# slambot.net
KiCad netlist of a schematic drawn in EAGLE
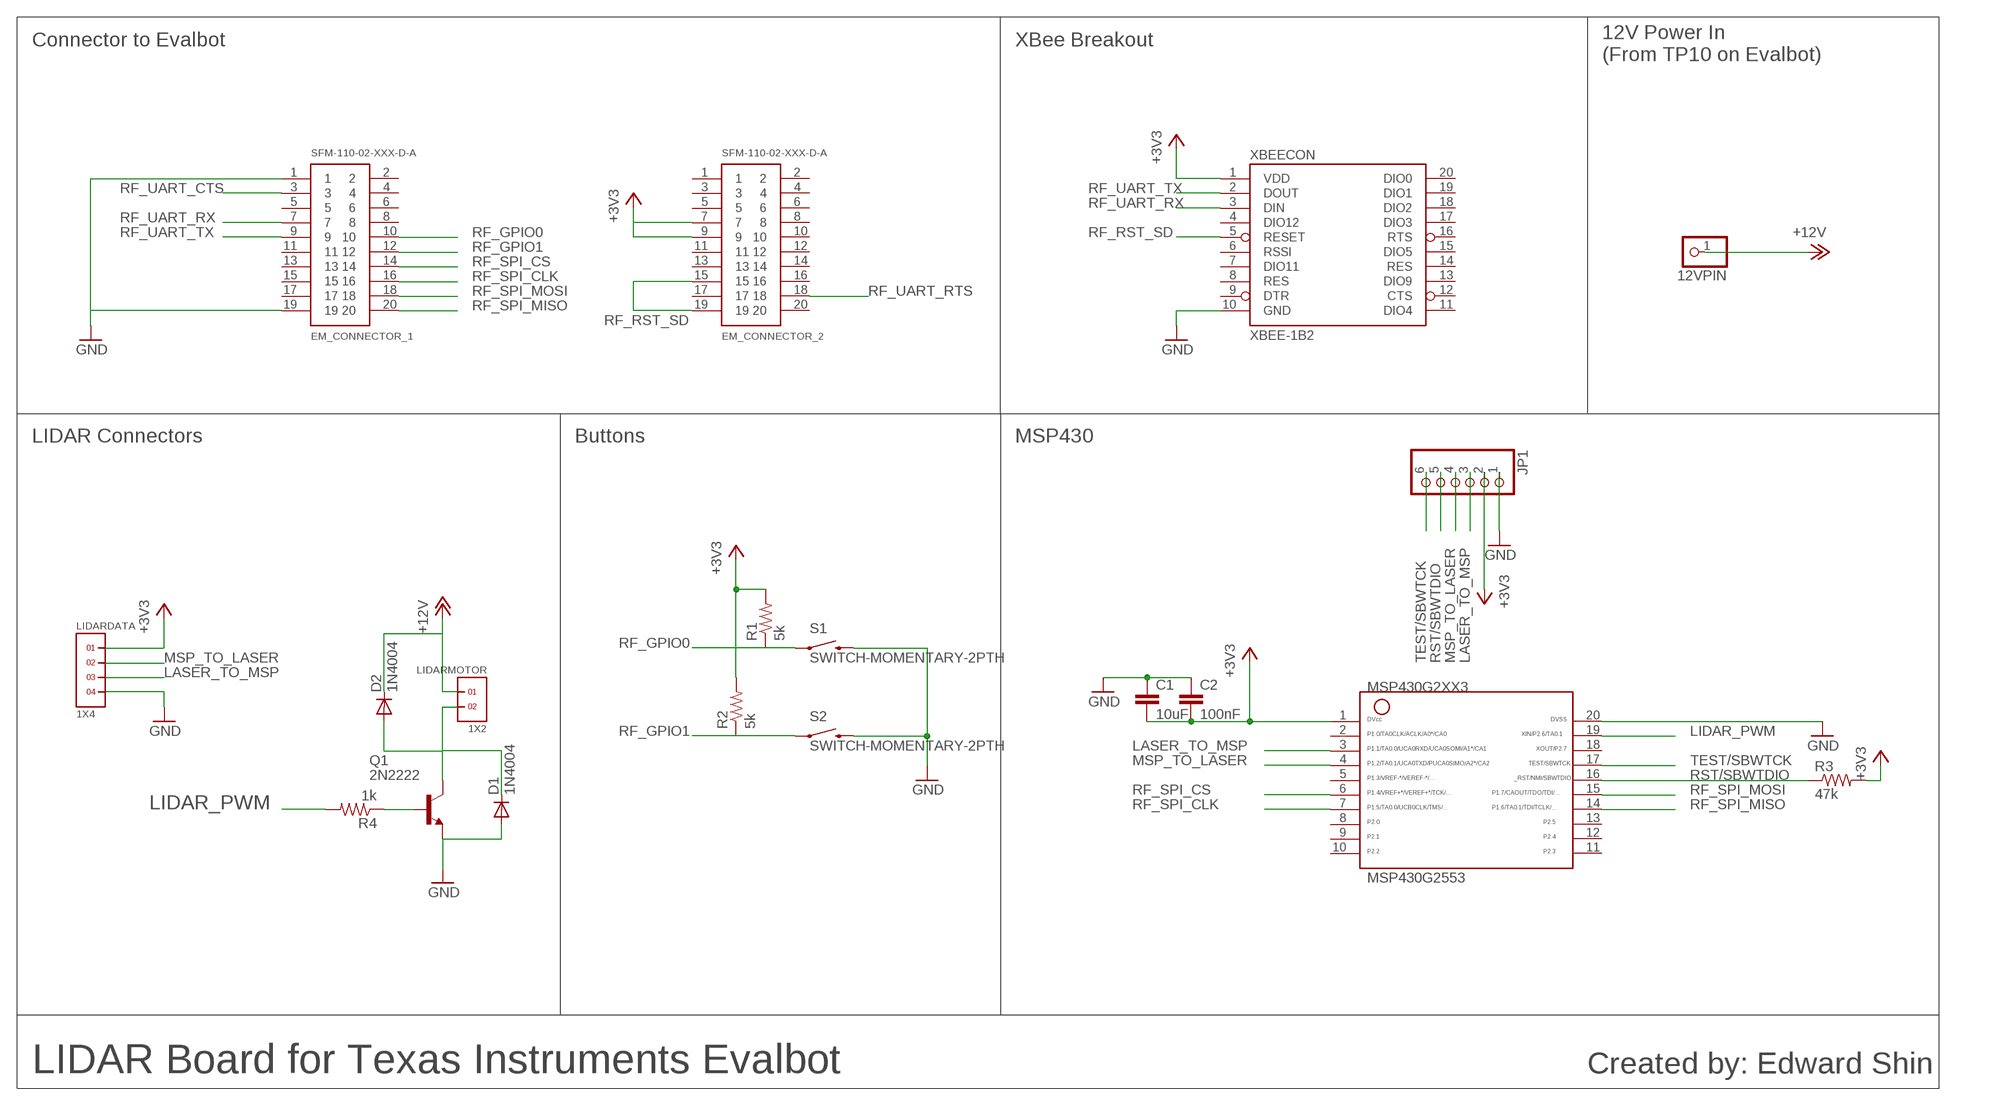
[diagram p0: schematic, sheet 1]

(export (version "E")
  (design (tool "Eeschema 10.0.6"))
  (components
    (comp (ref "12VPIN")
      (value "PINHD-1X1")
      (footprint "eagle-import:1X01")
      (libsource (lib "eagle-import") (part "PINHD-1X1"))
    )
    (comp (ref "C1")
      (value "10uF")
      (footprint "eagle-import:C2.5-2")
      (libsource (lib "eagle-import") (part "C2.5/2"))
    )
    (comp (ref "C2")
      (value "100nF")
      (footprint "eagle-import:C2.5-2")
      (libsource (lib "eagle-import") (part "C2.5/2"))
    )
    (comp (ref "D1")
      (value "1N4004")
      (footprint "eagle-import:DO41-10")
      (libsource (lib "eagle-import") (part "1N4004"))
    )
    (comp (ref "D2")
      (value "1N4004")
      (footprint "eagle-import:DO41-10")
      (libsource (lib "eagle-import") (part "1N4004"))
    )
    (comp (ref "EM_CONNECTOR_1")
      (value "SFM-110-02-XXX-D-A")
      (footprint "eagle-import:SFM-110-02-XXX-D-A")
      (libsource (lib "eagle-import") (part "SFM-110-02-XXX-D-A"))
    )
    (comp (ref "EM_CONNECTOR_2")
      (value "SFM-110-02-XXX-D-A")
      (footprint "eagle-import:SFM-110-02-XXX-D-A")
      (libsource (lib "eagle-import") (part "SFM-110-02-XXX-D-A"))
    )
    (comp (ref "JP1")
      (value "PINHD-1X6")
      (footprint "eagle-import:1X06")
      (libsource (lib "eagle-import") (part "PINHD-1X6"))
    )
    (comp (ref "LIDARDATA")
      (value "1X4")
      (footprint "eagle-import:1X4")
      (libsource (lib "eagle-import") (part "1X4"))
    )
    (comp (ref "LIDARMOTOR")
      (value "1X2")
      (footprint "eagle-import:1X2")
      (libsource (lib "eagle-import") (part "1X2"))
    )
    (comp (ref "MSP430G2553")
      (value "G2XX3---N20")
      (footprint "eagle-import:N20")
      (libsource (lib "eagle-import") (part "G2XX3---N20"))
    )
    (comp (ref "Q1")
      (value "2N2222")
      (footprint "eagle-import:TO18")
      (libsource (lib "eagle-import") (part "2N2222"))
    )
    (comp (ref "R1")
      (value "5k")
      (footprint "eagle-import:0309_12")
      (libsource (lib "eagle-import") (part "R-US_0309/12"))
    )
    (comp (ref "R2")
      (value "5k")
      (footprint "eagle-import:0309_12")
      (libsource (lib "eagle-import") (part "R-US_0309/12"))
    )
    (comp (ref "R3")
      (value "47k")
      (footprint "eagle-import:0309_12")
      (libsource (lib "eagle-import") (part "R-US_0309/12"))
    )
    (comp (ref "R4")
      (value "1k")
      (footprint "eagle-import:0309_12")
      (libsource (lib "eagle-import") (part "R-US_0309/12"))
    )
    (comp (ref "S1")
      (value "SWITCH-MOMENTARY-2PTH")
      (footprint "eagle-import:TACTILE-PTH")
      (libsource (lib "eagle-import") (part "SWITCH-MOMENTARY-2PTH"))
    )
    (comp (ref "S2")
      (value "SWITCH-MOMENTARY-2PTH")
      (footprint "eagle-import:TACTILE-PTH")
      (libsource (lib "eagle-import") (part "SWITCH-MOMENTARY-2PTH"))
    )
    (comp (ref "XBEECON")
      (value "XBEE-1B2")
      (footprint "eagle-import:XBEE-SILK")
      (libsource (lib "eagle-import") (part "XBEE-1B2"))
    )
  )
  (nets
    (net (code "1") (name "+3V3") (class "Default")
      (node (ref "C1") (pin "2") (pinfunction "2_2") (pintype "passive"))
      (node (ref "C2") (pin "2") (pinfunction "2_2") (pintype "passive"))
      (node (ref "EM_CONNECTOR_2") (pin "7") (pinfunction "7_7") (pintype "bidirectional"))
      (node (ref "EM_CONNECTOR_2") (pin "9") (pinfunction "9_9") (pintype "bidirectional"))
      (node (ref "JP1") (pin "2") (pinfunction "2_2") (pintype "passive"))
      (node (ref "LIDARDATA") (pin "1") (pinfunction "1_1") (pintype "bidirectional"))
      (node (ref "MSP430G2553") (pin "1") (pinfunction "1_1") (pintype "bidirectional"))
      (node (ref "R1") (pin "2") (pinfunction "2_2") (pintype "passive"))
      (node (ref "R2") (pin "2") (pinfunction "2_2") (pintype "passive"))
      (node (ref "R3") (pin "2") (pinfunction "2_2") (pintype "passive"))
      (node (ref "XBEECON") (pin "1") (pinfunction "VDD_1") (pintype "power_in"))
    )
    (net (code "2") (name "+12V") (class "Default")
      (node (ref "12VPIN") (pin "1") (pinfunction "1_1") (pintype "passive"))
      (node (ref "D2") (pin "C") (pinfunction "C_C") (pintype "passive"))
      (node (ref "LIDARMOTOR") (pin "1") (pinfunction "1_1") (pintype "bidirectional"))
    )
    (net (code "3") (name "/LASER_TO_MSP") (class "Default")
      (node (ref "JP1") (pin "3") (pinfunction "3_3") (pintype "passive"))
      (node (ref "LIDARDATA") (pin "3") (pinfunction "3_3") (pintype "bidirectional"))
      (node (ref "MSP430G2553") (pin "3") (pinfunction "3_3") (pintype "bidirectional"))
    )
    (net (code "4") (name "/LIDAR_PWM") (class "Default")
      (node (ref "MSP430G2553") (pin "19") (pinfunction "19_19") (pintype "bidirectional"))
      (node (ref "R4") (pin "2") (pinfunction "2_2") (pintype "passive"))
    )
    (net (code "5") (name "/MSP_TO_LASER") (class "Default")
      (node (ref "JP1") (pin "4") (pinfunction "4_4") (pintype "passive"))
      (node (ref "LIDARDATA") (pin "2") (pinfunction "2_2") (pintype "bidirectional"))
      (node (ref "MSP430G2553") (pin "4") (pinfunction "4_4") (pintype "bidirectional"))
    )
    (net (code "6") (name "/RF_GPIO0") (class "Default")
      (node (ref "EM_CONNECTOR_1") (pin "10") (pinfunction "10_10") (pintype "bidirectional"))
      (node (ref "R1") (pin "1") (pinfunction "1_1") (pintype "passive"))
      (node (ref "S1") (pin "1") (pinfunction "1_1") (pintype "passive"))
    )
    (net (code "7") (name "/RF_GPIO1") (class "Default")
      (node (ref "EM_CONNECTOR_1") (pin "12") (pinfunction "12_12") (pintype "bidirectional"))
      (node (ref "R2") (pin "1") (pinfunction "1_1") (pintype "passive"))
      (node (ref "S2") (pin "1") (pinfunction "1_1") (pintype "passive"))
    )
    (net (code "8") (name "/RF_RST_SD") (class "Default")
      (node (ref "EM_CONNECTOR_2") (pin "15") (pinfunction "15_15") (pintype "bidirectional"))
      (node (ref "EM_CONNECTOR_2") (pin "19") (pinfunction "19_19") (pintype "bidirectional"))
      (node (ref "XBEECON") (pin "5") (pinfunction "RESET_5") (pintype "input"))
    )
    (net (code "9") (name "/RF_SPI_CLK") (class "Default")
      (node (ref "EM_CONNECTOR_1") (pin "16") (pinfunction "16_16") (pintype "bidirectional"))
      (node (ref "MSP430G2553") (pin "7") (pinfunction "7_7") (pintype "bidirectional"))
    )
    (net (code "10") (name "/RF_SPI_CS") (class "Default")
      (node (ref "EM_CONNECTOR_1") (pin "14") (pinfunction "14_14") (pintype "bidirectional"))
      (node (ref "MSP430G2553") (pin "6") (pinfunction "6_6") (pintype "bidirectional"))
    )
    (net (code "11") (name "/RF_SPI_MISO") (class "Default")
      (node (ref "EM_CONNECTOR_1") (pin "20") (pinfunction "20_20") (pintype "bidirectional"))
      (node (ref "MSP430G2553") (pin "14") (pinfunction "14_14") (pintype "bidirectional"))
    )
    (net (code "12") (name "/RF_SPI_MOSI") (class "Default")
      (node (ref "EM_CONNECTOR_1") (pin "18") (pinfunction "18_18") (pintype "bidirectional"))
      (node (ref "MSP430G2553") (pin "15") (pinfunction "15_15") (pintype "bidirectional"))
    )
    (net (code "13") (name "/RF_UART_CTS") (class "Default")
      (node (ref "EM_CONNECTOR_1") (pin "3") (pinfunction "3_3") (pintype "bidirectional"))
    )
    (net (code "14") (name "/RF_UART_RTS") (class "Default")
      (node (ref "EM_CONNECTOR_2") (pin "18") (pinfunction "18_18") (pintype "bidirectional"))
    )
    (net (code "15") (name "/RF_UART_RX") (class "Default")
      (node (ref "EM_CONNECTOR_1") (pin "7") (pinfunction "7_7") (pintype "bidirectional"))
      (node (ref "XBEECON") (pin "3") (pinfunction "DIN_3") (pintype "input"))
    )
    (net (code "16") (name "/RF_UART_TX") (class "Default")
      (node (ref "EM_CONNECTOR_1") (pin "9") (pinfunction "9_9") (pintype "bidirectional"))
      (node (ref "XBEECON") (pin "2") (pinfunction "DOUT_2") (pintype "output"))
    )
    (net (code "17") (name "/RST{slash}SBWTDIO") (class "Default")
      (node (ref "JP1") (pin "5") (pinfunction "5_5") (pintype "passive"))
      (node (ref "MSP430G2553") (pin "16") (pinfunction "16_16") (pintype "bidirectional"))
      (node (ref "R3") (pin "1") (pinfunction "1_1") (pintype "passive"))
    )
    (net (code "18") (name "/TEST{slash}SBWTCK") (class "Default")
      (node (ref "JP1") (pin "6") (pinfunction "6_6") (pintype "passive"))
      (node (ref "MSP430G2553") (pin "17") (pinfunction "17_17") (pintype "bidirectional"))
    )
    (net (code "19") (name "GND") (class "Default")
      (node (ref "C1") (pin "1") (pinfunction "1_1") (pintype "passive"))
      (node (ref "C2") (pin "1") (pinfunction "1_1") (pintype "passive"))
      (node (ref "D1") (pin "A") (pinfunction "A_A") (pintype "passive"))
      (node (ref "EM_CONNECTOR_1") (pin "1") (pinfunction "1_1") (pintype "bidirectional"))
      (node (ref "EM_CONNECTOR_1") (pin "19") (pinfunction "19_19") (pintype "bidirectional"))
      (node (ref "JP1") (pin "1") (pinfunction "1_1") (pintype "passive"))
      (node (ref "LIDARDATA") (pin "4") (pinfunction "4_4") (pintype "bidirectional"))
      (node (ref "MSP430G2553") (pin "20") (pinfunction "20_20") (pintype "bidirectional"))
      (node (ref "Q1") (pin "1") (pinfunction "E_1") (pintype "passive"))
      (node (ref "S1") (pin "3") (pinfunction "2_3") (pintype "passive"))
      (node (ref "S2") (pin "3") (pinfunction "2_3") (pintype "passive"))
      (node (ref "XBEECON") (pin "10") (pinfunction "GND_10") (pintype "power_in"))
    )
    (net (code "20") (name "Net-(Q1-B)") (class "Default")
      (node (ref "Q1") (pin "2") (pinfunction "B_2") (pintype "passive"))
      (node (ref "R4") (pin "1") (pinfunction "1_1") (pintype "passive"))
    )
    (net (code "21") (name "Net-(Q1-C)") (class "Default")
      (node (ref "D1") (pin "C") (pinfunction "C_C") (pintype "passive"))
      (node (ref "D2") (pin "A") (pinfunction "A_A") (pintype "passive"))
      (node (ref "LIDARMOTOR") (pin "2") (pinfunction "2_2") (pintype "bidirectional"))
      (node (ref "Q1") (pin "3") (pinfunction "C_3") (pintype "passive"))
    )
    (net (code "22") (name "unconnected-(EM_CONNECTOR_1-Pad2)") (class "Default")
      (node (ref "EM_CONNECTOR_1") (pin "2") (pinfunction "2_2") (pintype "bidirectional"))
    )
    (net (code "23") (name "unconnected-(EM_CONNECTOR_1-Pad4)") (class "Default")
      (node (ref "EM_CONNECTOR_1") (pin "4") (pinfunction "4_4") (pintype "bidirectional"))
    )
    (net (code "24") (name "unconnected-(EM_CONNECTOR_1-Pad5)") (class "Default")
      (node (ref "EM_CONNECTOR_1") (pin "5") (pinfunction "5_5") (pintype "bidirectional"))
    )
    (net (code "25") (name "unconnected-(EM_CONNECTOR_1-Pad6)") (class "Default")
      (node (ref "EM_CONNECTOR_1") (pin "6") (pinfunction "6_6") (pintype "bidirectional"))
    )
    (net (code "26") (name "unconnected-(EM_CONNECTOR_1-Pad8)") (class "Default")
      (node (ref "EM_CONNECTOR_1") (pin "8") (pinfunction "8_8") (pintype "bidirectional"))
    )
    (net (code "27") (name "unconnected-(EM_CONNECTOR_1-Pad11)") (class "Default")
      (node (ref "EM_CONNECTOR_1") (pin "11") (pinfunction "11_11") (pintype "bidirectional"))
    )
    (net (code "28") (name "unconnected-(EM_CONNECTOR_1-Pad13)") (class "Default")
      (node (ref "EM_CONNECTOR_1") (pin "13") (pinfunction "13_13") (pintype "bidirectional"))
    )
    (net (code "29") (name "unconnected-(EM_CONNECTOR_1-Pad15)") (class "Default")
      (node (ref "EM_CONNECTOR_1") (pin "15") (pinfunction "15_15") (pintype "bidirectional"))
    )
    (net (code "30") (name "unconnected-(EM_CONNECTOR_1-Pad17)") (class "Default")
      (node (ref "EM_CONNECTOR_1") (pin "17") (pinfunction "17_17") (pintype "bidirectional"))
    )
    (net (code "31") (name "unconnected-(EM_CONNECTOR_2-Pad1)") (class "Default")
      (node (ref "EM_CONNECTOR_2") (pin "1") (pinfunction "1_1") (pintype "bidirectional"))
    )
    (net (code "32") (name "unconnected-(EM_CONNECTOR_2-Pad2)") (class "Default")
      (node (ref "EM_CONNECTOR_2") (pin "2") (pinfunction "2_2") (pintype "bidirectional"))
    )
    (net (code "33") (name "unconnected-(EM_CONNECTOR_2-Pad3)") (class "Default")
      (node (ref "EM_CONNECTOR_2") (pin "3") (pinfunction "3_3") (pintype "bidirectional"))
    )
    (net (code "34") (name "unconnected-(EM_CONNECTOR_2-Pad4)") (class "Default")
      (node (ref "EM_CONNECTOR_2") (pin "4") (pinfunction "4_4") (pintype "bidirectional"))
    )
    (net (code "35") (name "unconnected-(EM_CONNECTOR_2-Pad5)") (class "Default")
      (node (ref "EM_CONNECTOR_2") (pin "5") (pinfunction "5_5") (pintype "bidirectional"))
    )
    (net (code "36") (name "unconnected-(EM_CONNECTOR_2-Pad6)") (class "Default")
      (node (ref "EM_CONNECTOR_2") (pin "6") (pinfunction "6_6") (pintype "bidirectional"))
    )
    (net (code "37") (name "unconnected-(EM_CONNECTOR_2-Pad8)") (class "Default")
      (node (ref "EM_CONNECTOR_2") (pin "8") (pinfunction "8_8") (pintype "bidirectional"))
    )
    (net (code "38") (name "unconnected-(EM_CONNECTOR_2-Pad10)") (class "Default")
      (node (ref "EM_CONNECTOR_2") (pin "10") (pinfunction "10_10") (pintype "bidirectional"))
    )
    (net (code "39") (name "unconnected-(EM_CONNECTOR_2-Pad11)") (class "Default")
      (node (ref "EM_CONNECTOR_2") (pin "11") (pinfunction "11_11") (pintype "bidirectional"))
    )
    (net (code "40") (name "unconnected-(EM_CONNECTOR_2-Pad12)") (class "Default")
      (node (ref "EM_CONNECTOR_2") (pin "12") (pinfunction "12_12") (pintype "bidirectional"))
    )
    (net (code "41") (name "unconnected-(EM_CONNECTOR_2-Pad13)") (class "Default")
      (node (ref "EM_CONNECTOR_2") (pin "13") (pinfunction "13_13") (pintype "bidirectional"))
    )
    (net (code "42") (name "unconnected-(EM_CONNECTOR_2-Pad14)") (class "Default")
      (node (ref "EM_CONNECTOR_2") (pin "14") (pinfunction "14_14") (pintype "bidirectional"))
    )
    (net (code "43") (name "unconnected-(EM_CONNECTOR_2-Pad16)") (class "Default")
      (node (ref "EM_CONNECTOR_2") (pin "16") (pinfunction "16_16") (pintype "bidirectional"))
    )
    (net (code "44") (name "unconnected-(EM_CONNECTOR_2-Pad17)") (class "Default")
      (node (ref "EM_CONNECTOR_2") (pin "17") (pinfunction "17_17") (pintype "bidirectional"))
    )
    (net (code "45") (name "unconnected-(EM_CONNECTOR_2-Pad20)") (class "Default")
      (node (ref "EM_CONNECTOR_2") (pin "20") (pinfunction "20_20") (pintype "bidirectional"))
    )
    (net (code "46") (name "unconnected-(MSP430G2553-Pad2)") (class "Default")
      (node (ref "MSP430G2553") (pin "2") (pinfunction "2_2") (pintype "bidirectional"))
    )
    (net (code "47") (name "unconnected-(MSP430G2553-Pad5)") (class "Default")
      (node (ref "MSP430G2553") (pin "5") (pinfunction "5_5") (pintype "bidirectional"))
    )
    (net (code "48") (name "unconnected-(MSP430G2553-Pad8)") (class "Default")
      (node (ref "MSP430G2553") (pin "8") (pinfunction "8_8") (pintype "bidirectional"))
    )
    (net (code "49") (name "unconnected-(MSP430G2553-Pad9)") (class "Default")
      (node (ref "MSP430G2553") (pin "9") (pinfunction "9_9") (pintype "bidirectional"))
    )
    (net (code "50") (name "unconnected-(MSP430G2553-Pad10)") (class "Default")
      (node (ref "MSP430G2553") (pin "10") (pinfunction "10_10") (pintype "bidirectional"))
    )
    (net (code "51") (name "unconnected-(MSP430G2553-Pad11)") (class "Default")
      (node (ref "MSP430G2553") (pin "11") (pinfunction "11_11") (pintype "bidirectional"))
    )
    (net (code "52") (name "unconnected-(MSP430G2553-Pad12)") (class "Default")
      (node (ref "MSP430G2553") (pin "12") (pinfunction "12_12") (pintype "bidirectional"))
    )
    (net (code "53") (name "unconnected-(MSP430G2553-Pad13)") (class "Default")
      (node (ref "MSP430G2553") (pin "13") (pinfunction "13_13") (pintype "bidirectional"))
    )
    (net (code "54") (name "unconnected-(MSP430G2553-Pad18)") (class "Default")
      (node (ref "MSP430G2553") (pin "18") (pinfunction "18_18") (pintype "bidirectional"))
    )
    (net (code "55") (name "unconnected-(XBEECON-CTS-Pad12)") (class "Default")
      (node (ref "XBEECON") (pin "12") (pinfunction "CTS_12") (pintype "output"))
    )
    (net (code "56") (name "unconnected-(XBEECON-DIO0-Pad20)") (class "Default")
      (node (ref "XBEECON") (pin "20") (pinfunction "DIO0_20") (pintype "bidirectional"))
    )
    (net (code "57") (name "unconnected-(XBEECON-DIO1-Pad19)") (class "Default")
      (node (ref "XBEECON") (pin "19") (pinfunction "DIO1_19") (pintype "bidirectional"))
    )
    (net (code "58") (name "unconnected-(XBEECON-DIO2-Pad18)") (class "Default")
      (node (ref "XBEECON") (pin "18") (pinfunction "DIO2_18") (pintype "bidirectional"))
    )
    (net (code "59") (name "unconnected-(XBEECON-DIO3-Pad17)") (class "Default")
      (node (ref "XBEECON") (pin "17") (pinfunction "DIO3_17") (pintype "bidirectional"))
    )
    (net (code "60") (name "unconnected-(XBEECON-DIO4-Pad11)") (class "Default")
      (node (ref "XBEECON") (pin "11") (pinfunction "DIO4_11") (pintype "bidirectional"))
    )
    (net (code "61") (name "unconnected-(XBEECON-DIO5-Pad15)") (class "Default")
      (node (ref "XBEECON") (pin "15") (pinfunction "DIO5_15") (pintype "bidirectional"))
    )
    (net (code "62") (name "unconnected-(XBEECON-DIO9-Pad13)") (class "Default")
      (node (ref "XBEECON") (pin "13") (pinfunction "DIO9_13") (pintype "bidirectional"))
    )
    (net (code "63") (name "unconnected-(XBEECON-DIO11-Pad7)") (class "Default")
      (node (ref "XBEECON") (pin "7") (pinfunction "DIO11_7") (pintype "bidirectional"))
    )
    (net (code "64") (name "unconnected-(XBEECON-DIO12-Pad4)") (class "Default")
      (node (ref "XBEECON") (pin "4") (pinfunction "DIO12_4") (pintype "bidirectional"))
    )
    (net (code "65") (name "unconnected-(XBEECON-DTR-Pad9)") (class "Default")
      (node (ref "XBEECON") (pin "9") (pinfunction "DTR_9") (pintype "bidirectional"))
    )
    (net (code "66") (name "unconnected-(XBEECON-RES-Pad8)") (class "Default")
      (node (ref "XBEECON") (pin "8") (pinfunction "RES_8") (pintype "bidirectional"))
    )
    (net (code "67") (name "unconnected-(XBEECON-RES-Pad14)") (class "Default")
      (node (ref "XBEECON") (pin "14") (pinfunction "RES_14") (pintype "bidirectional"))
    )
    (net (code "68") (name "unconnected-(XBEECON-RSSI-Pad6)") (class "Default")
      (node (ref "XBEECON") (pin "6") (pinfunction "RSSI_6") (pintype "bidirectional"))
    )
    (net (code "69") (name "unconnected-(XBEECON-RTS-Pad16)") (class "Default")
      (node (ref "XBEECON") (pin "16") (pinfunction "RTS_16") (pintype "input"))
    )
  )
)
